# Channel.net
KiCad netlist of a schematic drawn in Altium Designer
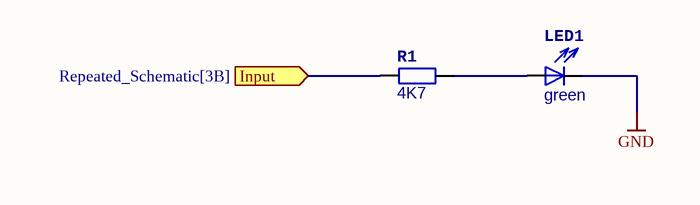
[diagram p0: Channel.SchDoc]

(export (version "E")
  (design (tool "Eeschema 10.0.6"))
  (components
    (comp (ref "LED1")
      (value "green")
      (footprint "LED0603")
      (description "GREEN LED, 0603, 430mcd, 140°, VF 3.2V, VR 5V")
      (libsource (lib "DUO_Opto") (part "LED_0603_GREEN"))
    )
    (comp (ref "R1")
      (value "4K7")
      (footprint "R0603")
      (description "4k7,  1%, TK100, 0.1W")
      (libsource (lib "DUO_R") (part "4K7-0603"))
    )
  )
  (nets
    (net (code "1") (name "/Input") (class "Default")
      (node (ref "R1") (pin "1") (pinfunction "1_1") (pintype "passive"))
    )
    (net (code "2") (name "GND") (class "Default")
      (node (ref "LED1") (pin "C") (pinfunction "C_C") (pintype "passive"))
    )
    (net (code "3") (name "Net-(LED1-PadA)") (class "Default")
      (node (ref "LED1") (pin "A") (pinfunction "A_A") (pintype "passive"))
      (node (ref "R1") (pin "2") (pinfunction "2_2") (pintype "passive"))
    )
  )
)
